# wctl_relays.net
KiCad netlist of a schematic drawn in EAGLE
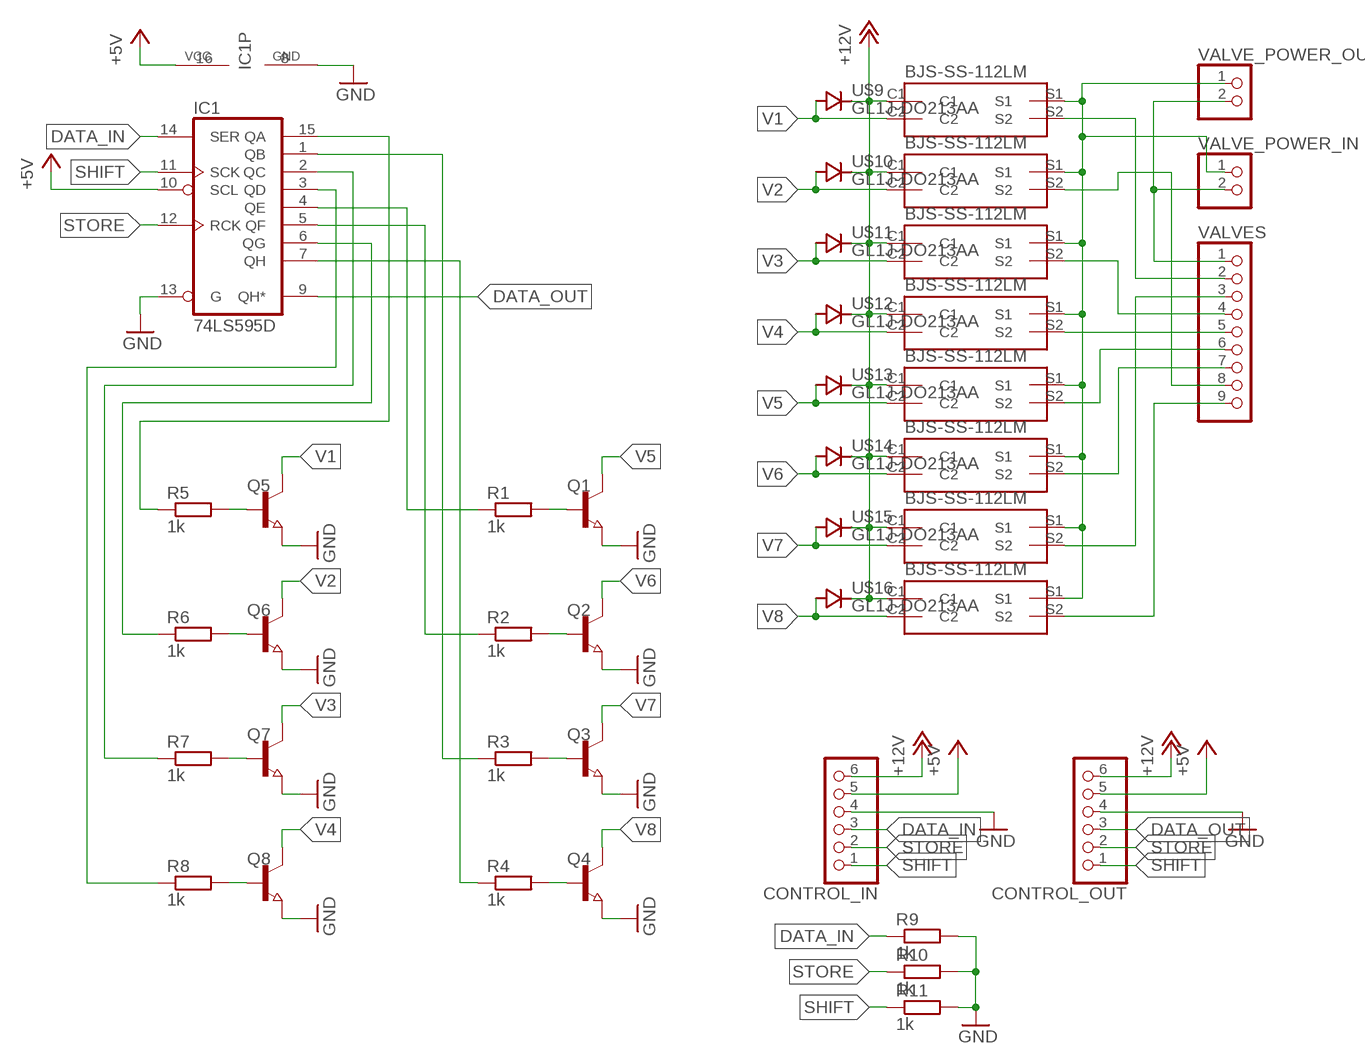
[diagram p0: schematic, sheet 1]

(export (version "E")
  (design (tool "Eeschema 10.0.6"))
  (components
    (comp (ref "CONTROL_IN")
      (value "PINHD-1X6")
      (footprint "eagle-import:1X06")
      (libsource (lib "eagle-import") (part "PINHD-1X6"))
    )
    (comp (ref "CONTROL_OUT")
      (value "PINHD-1X6")
      (footprint "eagle-import:1X06")
      (libsource (lib "eagle-import") (part "PINHD-1X6"))
    )
    (comp (ref "IC1")
      (value "74LS595D")
      (footprint "eagle-import:SO16")
      (libsource (lib "eagle-import") (part "74595DLS"))
    )
    (comp (ref "Q1")
      (value "NPN-TRANSISTOR_SOT23")
      (footprint "eagle-import:SOT23")
      (libsource (lib "eagle-import") (part "NPN-TRANSISTOR_SOT23"))
    )
    (comp (ref "Q2")
      (value "NPN-TRANSISTOR_SOT23")
      (footprint "eagle-import:SOT23")
      (libsource (lib "eagle-import") (part "NPN-TRANSISTOR_SOT23"))
    )
    (comp (ref "Q3")
      (value "NPN-TRANSISTOR_SOT23")
      (footprint "eagle-import:SOT23")
      (libsource (lib "eagle-import") (part "NPN-TRANSISTOR_SOT23"))
    )
    (comp (ref "Q4")
      (value "NPN-TRANSISTOR_SOT23")
      (footprint "eagle-import:SOT23")
      (libsource (lib "eagle-import") (part "NPN-TRANSISTOR_SOT23"))
    )
    (comp (ref "Q5")
      (value "NPN-TRANSISTOR_SOT23")
      (footprint "eagle-import:SOT23")
      (libsource (lib "eagle-import") (part "NPN-TRANSISTOR_SOT23"))
    )
    (comp (ref "Q6")
      (value "NPN-TRANSISTOR_SOT23")
      (footprint "eagle-import:SOT23")
      (libsource (lib "eagle-import") (part "NPN-TRANSISTOR_SOT23"))
    )
    (comp (ref "Q7")
      (value "NPN-TRANSISTOR_SOT23")
      (footprint "eagle-import:SOT23")
      (libsource (lib "eagle-import") (part "NPN-TRANSISTOR_SOT23"))
    )
    (comp (ref "Q8")
      (value "NPN-TRANSISTOR_SOT23")
      (footprint "eagle-import:SOT23")
      (libsource (lib "eagle-import") (part "NPN-TRANSISTOR_SOT23"))
    )
    (comp (ref "R1")
      (value "1k")
      (footprint "eagle-import:R0603")
      (libsource (lib "eagle-import") (part "R-EU_R0603"))
    )
    (comp (ref "R2")
      (value "1k")
      (footprint "eagle-import:R0603")
      (libsource (lib "eagle-import") (part "R-EU_R0603"))
    )
    (comp (ref "R3")
      (value "1k")
      (footprint "eagle-import:R0603")
      (libsource (lib "eagle-import") (part "R-EU_R0603"))
    )
    (comp (ref "R4")
      (value "1k")
      (footprint "eagle-import:R0603")
      (libsource (lib "eagle-import") (part "R-EU_R0603"))
    )
    (comp (ref "R5")
      (value "1k")
      (footprint "eagle-import:R0603")
      (libsource (lib "eagle-import") (part "R-EU_R0603"))
    )
    (comp (ref "R6")
      (value "1k")
      (footprint "eagle-import:R0603")
      (libsource (lib "eagle-import") (part "R-EU_R0603"))
    )
    (comp (ref "R7")
      (value "1k")
      (footprint "eagle-import:R0603")
      (libsource (lib "eagle-import") (part "R-EU_R0603"))
    )
    (comp (ref "R8")
      (value "1k")
      (footprint "eagle-import:R0603")
      (libsource (lib "eagle-import") (part "R-EU_R0603"))
    )
    (comp (ref "R9")
      (value "1k")
      (footprint "eagle-import:R0603")
      (libsource (lib "eagle-import") (part "R-EU_R0603"))
    )
    (comp (ref "R10")
      (value "1k")
      (footprint "eagle-import:R0603")
      (libsource (lib "eagle-import") (part "R-EU_R0603"))
    )
    (comp (ref "R11")
      (value "1k")
      (footprint "eagle-import:R0603")
      (libsource (lib "eagle-import") (part "R-EU_R0603"))
    )
    (comp (ref "U$1")
      (value "BJS-SS-112LM")
      (footprint "eagle-import:BJS-SS-112LM")
      (libsource (lib "eagle-import") (part "BJS-SS-112LM"))
    )
    (comp (ref "U$2")
      (value "BJS-SS-112LM")
      (footprint "eagle-import:BJS-SS-112LM")
      (libsource (lib "eagle-import") (part "BJS-SS-112LM"))
    )
    (comp (ref "U$3")
      (value "BJS-SS-112LM")
      (footprint "eagle-import:BJS-SS-112LM")
      (libsource (lib "eagle-import") (part "BJS-SS-112LM"))
    )
    (comp (ref "U$4")
      (value "BJS-SS-112LM")
      (footprint "eagle-import:BJS-SS-112LM")
      (libsource (lib "eagle-import") (part "BJS-SS-112LM"))
    )
    (comp (ref "U$5")
      (value "BJS-SS-112LM")
      (footprint "eagle-import:BJS-SS-112LM")
      (libsource (lib "eagle-import") (part "BJS-SS-112LM"))
    )
    (comp (ref "U$6")
      (value "BJS-SS-112LM")
      (footprint "eagle-import:BJS-SS-112LM")
      (libsource (lib "eagle-import") (part "BJS-SS-112LM"))
    )
    (comp (ref "U$7")
      (value "BJS-SS-112LM")
      (footprint "eagle-import:BJS-SS-112LM")
      (libsource (lib "eagle-import") (part "BJS-SS-112LM"))
    )
    (comp (ref "U$8")
      (value "BJS-SS-112LM")
      (footprint "eagle-import:BJS-SS-112LM")
      (libsource (lib "eagle-import") (part "BJS-SS-112LM"))
    )
    (comp (ref "U$9")
      (value "GL1J-DO213AA")
      (footprint "eagle-import:GL1J-DO213AA")
      (libsource (lib "eagle-import") (part "GL1J-DO213AA"))
    )
    (comp (ref "U$10")
      (value "GL1J-DO213AA")
      (footprint "eagle-import:GL1J-DO213AA")
      (libsource (lib "eagle-import") (part "GL1J-DO213AA"))
    )
    (comp (ref "U$11")
      (value "GL1J-DO213AA")
      (footprint "eagle-import:GL1J-DO213AA")
      (libsource (lib "eagle-import") (part "GL1J-DO213AA"))
    )
    (comp (ref "U$12")
      (value "GL1J-DO213AA")
      (footprint "eagle-import:GL1J-DO213AA")
      (libsource (lib "eagle-import") (part "GL1J-DO213AA"))
    )
    (comp (ref "U$13")
      (value "GL1J-DO213AA")
      (footprint "eagle-import:GL1J-DO213AA")
      (libsource (lib "eagle-import") (part "GL1J-DO213AA"))
    )
    (comp (ref "U$14")
      (value "GL1J-DO213AA")
      (footprint "eagle-import:GL1J-DO213AA")
      (libsource (lib "eagle-import") (part "GL1J-DO213AA"))
    )
    (comp (ref "U$15")
      (value "GL1J-DO213AA")
      (footprint "eagle-import:GL1J-DO213AA")
      (libsource (lib "eagle-import") (part "GL1J-DO213AA"))
    )
    (comp (ref "U$16")
      (value "GL1J-DO213AA")
      (footprint "eagle-import:GL1J-DO213AA")
      (libsource (lib "eagle-import") (part "GL1J-DO213AA"))
    )
    (comp (ref "VALVES")
      (value "PINHD-1X9")
      (footprint "eagle-import:1X09")
      (libsource (lib "eagle-import") (part "PINHD-1X9"))
    )
    (comp (ref "VALVE_POWER_IN")
      (value "PINHD-1X2")
      (footprint "eagle-import:1X02")
      (libsource (lib "eagle-import") (part "PINHD-1X2"))
    )
    (comp (ref "VALVE_POWER_OUT")
      (value "PINHD-1X2")
      (footprint "eagle-import:1X02")
      (libsource (lib "eagle-import") (part "PINHD-1X2"))
    )
  )
  (nets
    (net (code "1") (name "+5V") (class "Default")
      (node (ref "CONTROL_IN") (pin "5") (pinfunction "5_5") (pintype "passive"))
      (node (ref "CONTROL_OUT") (pin "5") (pinfunction "5_5") (pintype "passive"))
      (node (ref "IC1") (pin "10") (pinfunction "SCL_10") (pintype "input"))
      (node (ref "IC1") (pin "16") (pinfunction "VCC_16") (pintype "power_in"))
    )
    (net (code "2") (name "+12V") (class "Default")
      (node (ref "CONTROL_IN") (pin "6") (pinfunction "6_6") (pintype "passive"))
      (node (ref "CONTROL_OUT") (pin "6") (pinfunction "6_6") (pintype "passive"))
      (node (ref "U$1") (pin "C1") (pinfunction "C1_C1") (pintype "bidirectional"))
      (node (ref "U$10") (pin "C") (pinfunction "C_C") (pintype "passive"))
      (node (ref "U$11") (pin "C") (pinfunction "C_C") (pintype "passive"))
      (node (ref "U$12") (pin "C") (pinfunction "C_C") (pintype "passive"))
      (node (ref "U$13") (pin "C") (pinfunction "C_C") (pintype "passive"))
      (node (ref "U$14") (pin "C") (pinfunction "C_C") (pintype "passive"))
      (node (ref "U$15") (pin "C") (pinfunction "C_C") (pintype "passive"))
      (node (ref "U$16") (pin "C") (pinfunction "C_C") (pintype "passive"))
      (node (ref "U$2") (pin "C1") (pinfunction "C1_C1") (pintype "bidirectional"))
      (node (ref "U$3") (pin "C1") (pinfunction "C1_C1") (pintype "bidirectional"))
      (node (ref "U$4") (pin "C1") (pinfunction "C1_C1") (pintype "bidirectional"))
      (node (ref "U$5") (pin "C1") (pinfunction "C1_C1") (pintype "bidirectional"))
      (node (ref "U$6") (pin "C1") (pinfunction "C1_C1") (pintype "bidirectional"))
      (node (ref "U$7") (pin "C1") (pinfunction "C1_C1") (pintype "bidirectional"))
      (node (ref "U$8") (pin "C1") (pinfunction "C1_C1") (pintype "bidirectional"))
      (node (ref "U$9") (pin "C") (pinfunction "C_C") (pintype "passive"))
    )
    (net (code "3") (name "DATA_IN") (class "Default")
      (node (ref "CONTROL_IN") (pin "3") (pinfunction "3_3") (pintype "passive"))
      (node (ref "IC1") (pin "14") (pinfunction "SER_14") (pintype "input"))
      (node (ref "R9") (pin "1") (pinfunction "1_1") (pintype "passive"))
    )
    (net (code "4") (name "DATA_OUT") (class "Default")
      (node (ref "CONTROL_OUT") (pin "3") (pinfunction "3_3") (pintype "passive"))
      (node (ref "IC1") (pin "9") (pinfunction "QH*_9") (pintype "tri_state"))
    )
    (net (code "5") (name "GND") (class "Default")
      (node (ref "CONTROL_IN") (pin "4") (pinfunction "4_4") (pintype "passive"))
      (node (ref "CONTROL_OUT") (pin "4") (pinfunction "4_4") (pintype "passive"))
      (node (ref "IC1") (pin "13") (pinfunction "G_13") (pintype "input"))
      (node (ref "IC1") (pin "8") (pinfunction "GND_8") (pintype "power_in"))
      (node (ref "Q1") (pin "2") (pinfunction "E_2") (pintype "passive"))
      (node (ref "Q2") (pin "2") (pinfunction "E_2") (pintype "passive"))
      (node (ref "Q3") (pin "2") (pinfunction "E_2") (pintype "passive"))
      (node (ref "Q4") (pin "2") (pinfunction "E_2") (pintype "passive"))
      (node (ref "Q5") (pin "2") (pinfunction "E_2") (pintype "passive"))
      (node (ref "Q6") (pin "2") (pinfunction "E_2") (pintype "passive"))
      (node (ref "Q7") (pin "2") (pinfunction "E_2") (pintype "passive"))
      (node (ref "Q8") (pin "2") (pinfunction "E_2") (pintype "passive"))
      (node (ref "R10") (pin "2") (pinfunction "2_2") (pintype "passive"))
      (node (ref "R11") (pin "2") (pinfunction "2_2") (pintype "passive"))
      (node (ref "R9") (pin "2") (pinfunction "2_2") (pintype "passive"))
    )
    (net (code "6") (name "Net-(IC1A-QA)") (class "Default")
      (node (ref "IC1") (pin "15") (pinfunction "QA_15") (pintype "tri_state"))
      (node (ref "R5") (pin "1") (pinfunction "1_1") (pintype "passive"))
    )
    (net (code "7") (name "Net-(IC1A-QB)") (class "Default")
      (node (ref "IC1") (pin "1") (pinfunction "QB_1") (pintype "tri_state"))
      (node (ref "R3") (pin "1") (pinfunction "1_1") (pintype "passive"))
    )
    (net (code "8") (name "Net-(IC1A-QC)") (class "Default")
      (node (ref "IC1") (pin "2") (pinfunction "QC_2") (pintype "tri_state"))
      (node (ref "R7") (pin "1") (pinfunction "1_1") (pintype "passive"))
    )
    (net (code "9") (name "Net-(IC1A-QD)") (class "Default")
      (node (ref "IC1") (pin "3") (pinfunction "QD_3") (pintype "tri_state"))
      (node (ref "R8") (pin "1") (pinfunction "1_1") (pintype "passive"))
    )
    (net (code "10") (name "Net-(IC1A-QE)") (class "Default")
      (node (ref "IC1") (pin "4") (pinfunction "QE_4") (pintype "tri_state"))
      (node (ref "R1") (pin "1") (pinfunction "1_1") (pintype "passive"))
    )
    (net (code "11") (name "Net-(IC1A-QF)") (class "Default")
      (node (ref "IC1") (pin "5") (pinfunction "QF_5") (pintype "tri_state"))
      (node (ref "R2") (pin "1") (pinfunction "1_1") (pintype "passive"))
    )
    (net (code "12") (name "Net-(IC1A-QG)") (class "Default")
      (node (ref "IC1") (pin "6") (pinfunction "QG_6") (pintype "tri_state"))
      (node (ref "R6") (pin "1") (pinfunction "1_1") (pintype "passive"))
    )
    (net (code "13") (name "Net-(IC1A-QH)") (class "Default")
      (node (ref "IC1") (pin "7") (pinfunction "QH_7") (pintype "tri_state"))
      (node (ref "R4") (pin "1") (pinfunction "1_1") (pintype "passive"))
    )
    (net (code "14") (name "Net-(Q1-B)") (class "Default")
      (node (ref "Q1") (pin "1") (pinfunction "B_1") (pintype "passive"))
      (node (ref "R1") (pin "2") (pinfunction "2_2") (pintype "passive"))
    )
    (net (code "15") (name "Net-(Q2-B)") (class "Default")
      (node (ref "Q2") (pin "1") (pinfunction "B_1") (pintype "passive"))
      (node (ref "R2") (pin "2") (pinfunction "2_2") (pintype "passive"))
    )
    (net (code "16") (name "Net-(Q3-B)") (class "Default")
      (node (ref "Q3") (pin "1") (pinfunction "B_1") (pintype "passive"))
      (node (ref "R3") (pin "2") (pinfunction "2_2") (pintype "passive"))
    )
    (net (code "17") (name "Net-(Q4-B)") (class "Default")
      (node (ref "Q4") (pin "1") (pinfunction "B_1") (pintype "passive"))
      (node (ref "R4") (pin "2") (pinfunction "2_2") (pintype "passive"))
    )
    (net (code "18") (name "Net-(Q5-B)") (class "Default")
      (node (ref "Q5") (pin "1") (pinfunction "B_1") (pintype "passive"))
      (node (ref "R5") (pin "2") (pinfunction "2_2") (pintype "passive"))
    )
    (net (code "19") (name "Net-(Q6-B)") (class "Default")
      (node (ref "Q6") (pin "1") (pinfunction "B_1") (pintype "passive"))
      (node (ref "R6") (pin "2") (pinfunction "2_2") (pintype "passive"))
    )
    (net (code "20") (name "Net-(Q7-B)") (class "Default")
      (node (ref "Q7") (pin "1") (pinfunction "B_1") (pintype "passive"))
      (node (ref "R7") (pin "2") (pinfunction "2_2") (pintype "passive"))
    )
    (net (code "21") (name "Net-(Q8-B)") (class "Default")
      (node (ref "Q8") (pin "1") (pinfunction "B_1") (pintype "passive"))
      (node (ref "R8") (pin "2") (pinfunction "2_2") (pintype "passive"))
    )
    (net (code "22") (name "Net-(U$1-PadS1)") (class "Default")
      (node (ref "U$1") (pin "S1") (pinfunction "S1_S1") (pintype "bidirectional"))
      (node (ref "U$2") (pin "S1") (pinfunction "S1_S1") (pintype "bidirectional"))
      (node (ref "U$3") (pin "S1") (pinfunction "S1_S1") (pintype "bidirectional"))
      (node (ref "U$4") (pin "S1") (pinfunction "S1_S1") (pintype "bidirectional"))
      (node (ref "U$5") (pin "S1") (pinfunction "S1_S1") (pintype "bidirectional"))
      (node (ref "U$6") (pin "S1") (pinfunction "S1_S1") (pintype "bidirectional"))
      (node (ref "U$7") (pin "S1") (pinfunction "S1_S1") (pintype "bidirectional"))
      (node (ref "U$8") (pin "S1") (pinfunction "S1_S1") (pintype "bidirectional"))
      (node (ref "VALVE_POWER_IN") (pin "1") (pinfunction "1_1") (pintype "passive"))
      (node (ref "VALVE_POWER_OUT") (pin "1") (pinfunction "1_1") (pintype "passive"))
    )
    (net (code "23") (name "Net-(U$1-PadS2)") (class "Default")
      (node (ref "U$1") (pin "S2") (pinfunction "S2_S2") (pintype "bidirectional"))
      (node (ref "VALVES") (pin "2") (pinfunction "2_2") (pintype "passive"))
    )
    (net (code "24") (name "Net-(U$2-PadS2)") (class "Default")
      (node (ref "U$2") (pin "S2") (pinfunction "S2_S2") (pintype "bidirectional"))
      (node (ref "VALVES") (pin "8") (pinfunction "8_8") (pintype "passive"))
    )
    (net (code "25") (name "Net-(U$3-PadS2)") (class "Default")
      (node (ref "U$3") (pin "S2") (pinfunction "S2_S2") (pintype "bidirectional"))
      (node (ref "VALVES") (pin "4") (pinfunction "4_4") (pintype "passive"))
    )
    (net (code "26") (name "Net-(U$4-PadS2)") (class "Default")
      (node (ref "U$4") (pin "S2") (pinfunction "S2_S2") (pintype "bidirectional"))
      (node (ref "VALVES") (pin "5") (pinfunction "5_5") (pintype "passive"))
    )
    (net (code "27") (name "Net-(U$5-PadS2)") (class "Default")
      (node (ref "U$5") (pin "S2") (pinfunction "S2_S2") (pintype "bidirectional"))
      (node (ref "VALVES") (pin "6") (pinfunction "6_6") (pintype "passive"))
    )
    (net (code "28") (name "Net-(U$6-PadS2)") (class "Default")
      (node (ref "U$6") (pin "S2") (pinfunction "S2_S2") (pintype "bidirectional"))
      (node (ref "VALVES") (pin "7") (pinfunction "7_7") (pintype "passive"))
    )
    (net (code "29") (name "Net-(U$7-PadS2)") (class "Default")
      (node (ref "U$7") (pin "S2") (pinfunction "S2_S2") (pintype "bidirectional"))
      (node (ref "VALVES") (pin "3") (pinfunction "3_3") (pintype "passive"))
    )
    (net (code "30") (name "Net-(U$8-PadS2)") (class "Default")
      (node (ref "U$8") (pin "S2") (pinfunction "S2_S2") (pintype "bidirectional"))
      (node (ref "VALVES") (pin "9") (pinfunction "9_9") (pintype "passive"))
    )
    (net (code "31") (name "Net-(VALVES-Pad1)") (class "Default")
      (node (ref "VALVES") (pin "1") (pinfunction "1_1") (pintype "passive"))
      (node (ref "VALVE_POWER_IN") (pin "2") (pinfunction "2_2") (pintype "passive"))
      (node (ref "VALVE_POWER_OUT") (pin "2") (pinfunction "2_2") (pintype "passive"))
    )
    (net (code "32") (name "SHIFT") (class "Default")
      (node (ref "CONTROL_IN") (pin "1") (pinfunction "1_1") (pintype "passive"))
      (node (ref "CONTROL_OUT") (pin "1") (pinfunction "1_1") (pintype "passive"))
      (node (ref "IC1") (pin "11") (pinfunction "SCK_11") (pintype "input"))
      (node (ref "R11") (pin "1") (pinfunction "1_1") (pintype "passive"))
    )
    (net (code "33") (name "STORE") (class "Default")
      (node (ref "CONTROL_IN") (pin "2") (pinfunction "2_2") (pintype "passive"))
      (node (ref "CONTROL_OUT") (pin "2") (pinfunction "2_2") (pintype "passive"))
      (node (ref "IC1") (pin "12") (pinfunction "RCK_12") (pintype "input"))
      (node (ref "R10") (pin "1") (pinfunction "1_1") (pintype "passive"))
    )
    (net (code "34") (name "V1") (class "Default")
      (node (ref "Q5") (pin "3") (pinfunction "C_3") (pintype "passive"))
      (node (ref "U$1") (pin "C2") (pinfunction "C2_C2") (pintype "bidirectional"))
      (node (ref "U$9") (pin "A") (pinfunction "A_A") (pintype "passive"))
    )
    (net (code "35") (name "V2") (class "Default")
      (node (ref "Q6") (pin "3") (pinfunction "C_3") (pintype "passive"))
      (node (ref "U$10") (pin "A") (pinfunction "A_A") (pintype "passive"))
      (node (ref "U$2") (pin "C2") (pinfunction "C2_C2") (pintype "bidirectional"))
    )
    (net (code "36") (name "V3") (class "Default")
      (node (ref "Q7") (pin "3") (pinfunction "C_3") (pintype "passive"))
      (node (ref "U$11") (pin "A") (pinfunction "A_A") (pintype "passive"))
      (node (ref "U$3") (pin "C2") (pinfunction "C2_C2") (pintype "bidirectional"))
    )
    (net (code "37") (name "V4") (class "Default")
      (node (ref "Q8") (pin "3") (pinfunction "C_3") (pintype "passive"))
      (node (ref "U$12") (pin "A") (pinfunction "A_A") (pintype "passive"))
      (node (ref "U$4") (pin "C2") (pinfunction "C2_C2") (pintype "bidirectional"))
    )
    (net (code "38") (name "V5") (class "Default")
      (node (ref "Q1") (pin "3") (pinfunction "C_3") (pintype "passive"))
      (node (ref "U$13") (pin "A") (pinfunction "A_A") (pintype "passive"))
      (node (ref "U$5") (pin "C2") (pinfunction "C2_C2") (pintype "bidirectional"))
    )
    (net (code "39") (name "V6") (class "Default")
      (node (ref "Q2") (pin "3") (pinfunction "C_3") (pintype "passive"))
      (node (ref "U$14") (pin "A") (pinfunction "A_A") (pintype "passive"))
      (node (ref "U$6") (pin "C2") (pinfunction "C2_C2") (pintype "bidirectional"))
    )
    (net (code "40") (name "V7") (class "Default")
      (node (ref "Q3") (pin "3") (pinfunction "C_3") (pintype "passive"))
      (node (ref "U$15") (pin "A") (pinfunction "A_A") (pintype "passive"))
      (node (ref "U$7") (pin "C2") (pinfunction "C2_C2") (pintype "bidirectional"))
    )
    (net (code "41") (name "V8") (class "Default")
      (node (ref "Q4") (pin "3") (pinfunction "C_3") (pintype "passive"))
      (node (ref "U$16") (pin "A") (pinfunction "A_A") (pintype "passive"))
      (node (ref "U$8") (pin "C2") (pinfunction "C2_C2") (pintype "bidirectional"))
    )
  )
)
